# PDB2.net
KiCad netlist of a schematic drawn in EAGLE
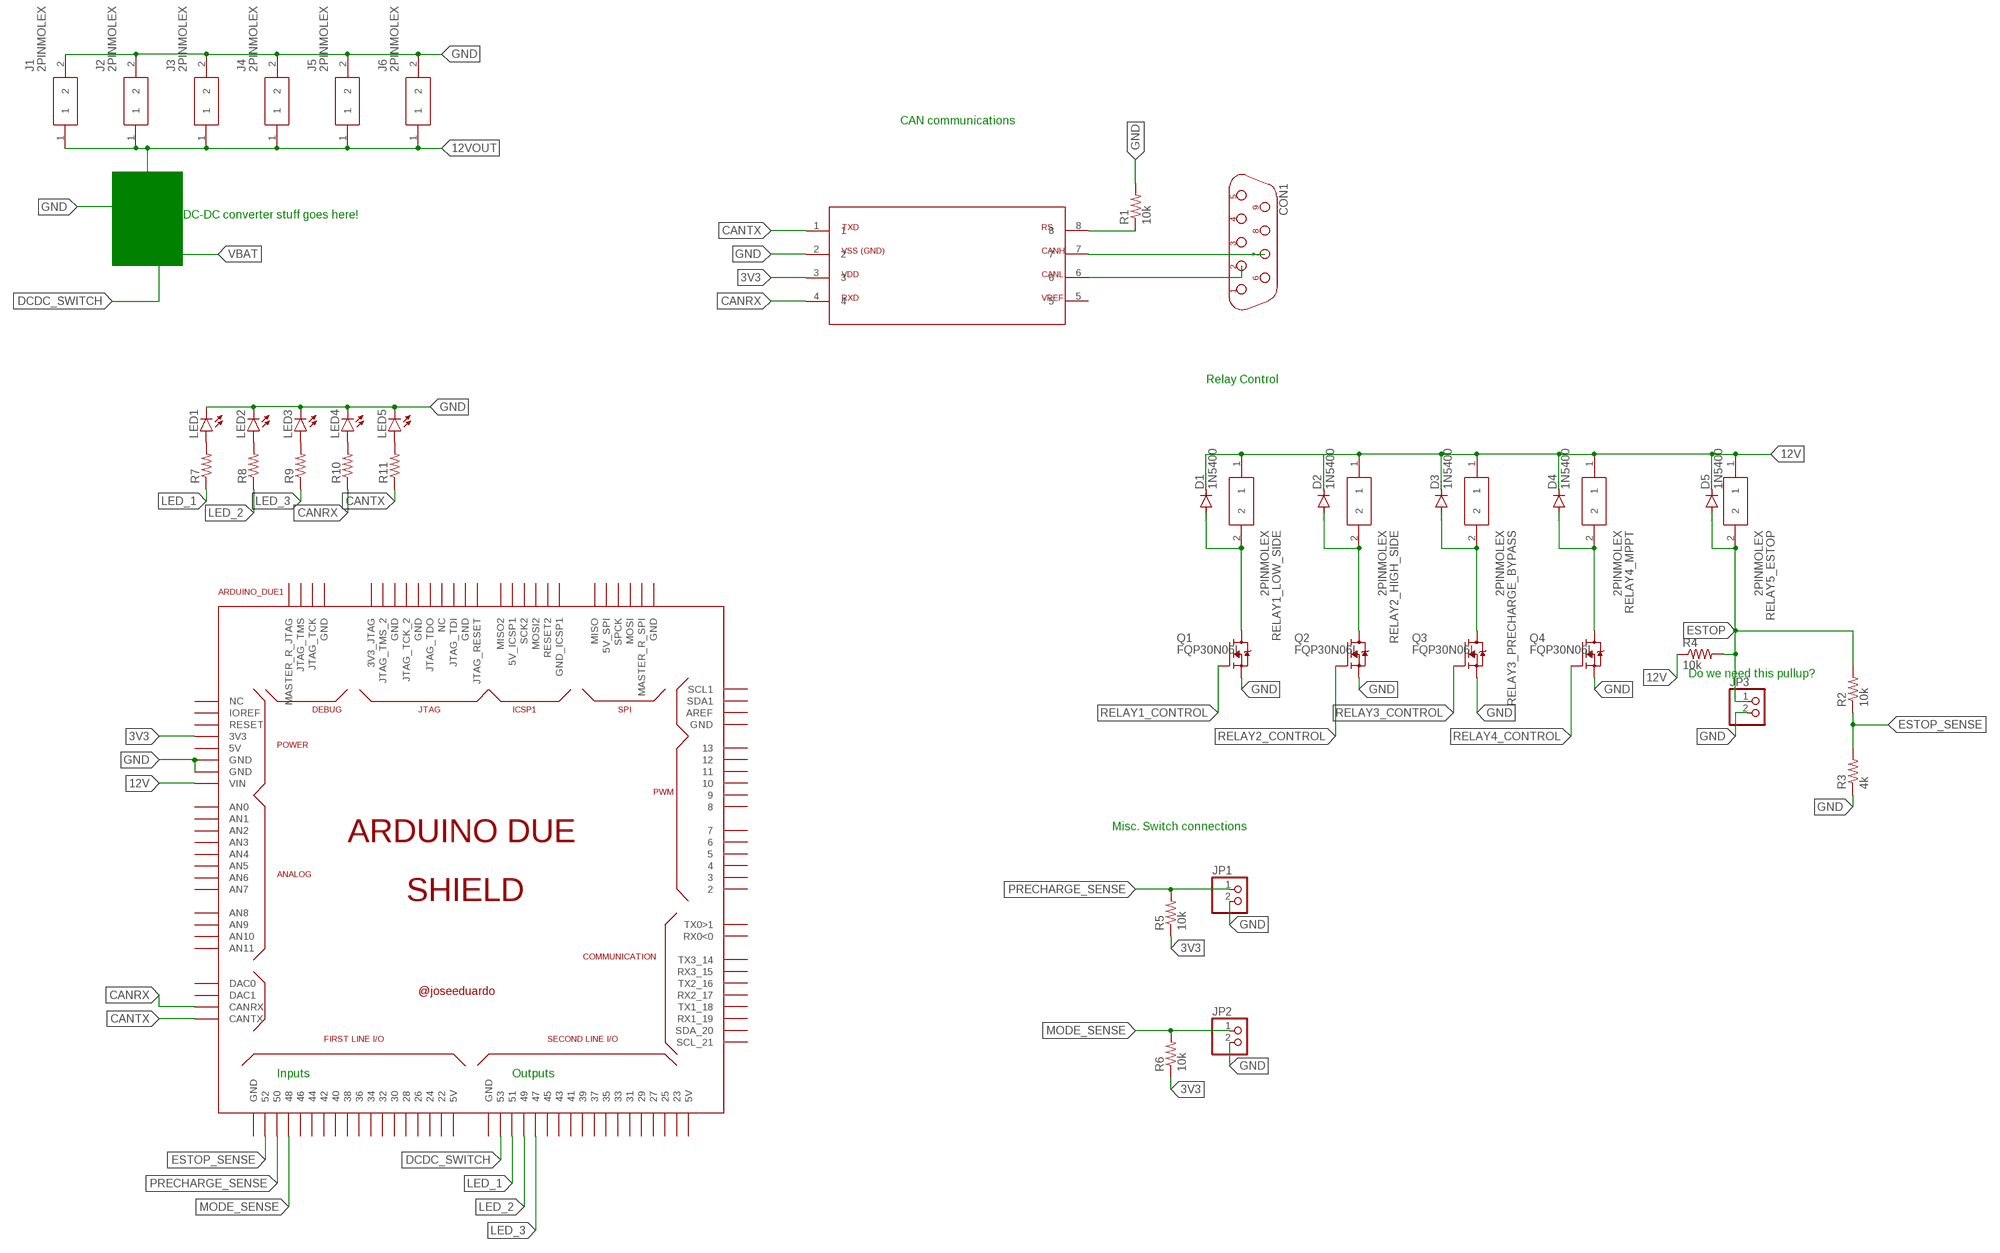
[diagram p0: schematic, sheet 1]

(export (version "E")
  (design (tool "Eeschema 10.0.6"))
  (components
    (comp (ref "ARDUINO_DUE1")
      (value "ARDUINO_DUE_SHIELD")
      (footprint "eagle-import:ARDUINO_DUE_SHIELD")
      (libsource (lib "eagle-import") (part "ARDUINO_DUE_SHIELD"))
    )
    (comp (ref "CON1")
      (value "DB9F")
      (footprint "eagle-import:D-09F")
      (libsource (lib "eagle-import") (part "DB9F"))
    )
    (comp (ref "D1")
      (value "1N5400")
      (footprint "eagle-import:DO201-15")
      (libsource (lib "eagle-import") (part "1N5400"))
    )
    (comp (ref "D2")
      (value "1N5400")
      (footprint "eagle-import:DO201-15")
      (libsource (lib "eagle-import") (part "1N5400"))
    )
    (comp (ref "D3")
      (value "1N5400")
      (footprint "eagle-import:DO201-15")
      (libsource (lib "eagle-import") (part "1N5400"))
    )
    (comp (ref "D4")
      (value "1N5400")
      (footprint "eagle-import:DO201-15")
      (libsource (lib "eagle-import") (part "1N5400"))
    )
    (comp (ref "D5")
      (value "1N5400")
      (footprint "eagle-import:DO201-15")
      (libsource (lib "eagle-import") (part "1N5400"))
    )
    (comp (ref "J1")
      (value "2PINMOLEX")
      (footprint "eagle-import:768250002")
      (fields
        (field (name "MANUFACTURER_PART_NUMBER") "76825-0002")
        (field (name "MOUSER_PART_NUMBER") "538-76825-0002")
        (field (name "RS_PART_NUMBER") "1790654")
      )
      (libsource (lib "eagle-import") (part "2PINMOLEX"))
    )
    (comp (ref "J2")
      (value "2PINMOLEX")
      (footprint "eagle-import:768250002")
      (fields
        (field (name "MANUFACTURER_PART_NUMBER") "76825-0002")
        (field (name "MOUSER_PART_NUMBER") "538-76825-0002")
        (field (name "RS_PART_NUMBER") "1790654")
      )
      (libsource (lib "eagle-import") (part "2PINMOLEX"))
    )
    (comp (ref "J3")
      (value "2PINMOLEX")
      (footprint "eagle-import:768250002")
      (fields
        (field (name "MANUFACTURER_PART_NUMBER") "76825-0002")
        (field (name "MOUSER_PART_NUMBER") "538-76825-0002")
        (field (name "RS_PART_NUMBER") "1790654")
      )
      (libsource (lib "eagle-import") (part "2PINMOLEX"))
    )
    (comp (ref "J4")
      (value "2PINMOLEX")
      (footprint "eagle-import:768250002")
      (fields
        (field (name "MANUFACTURER_PART_NUMBER") "76825-0002")
        (field (name "MOUSER_PART_NUMBER") "538-76825-0002")
        (field (name "RS_PART_NUMBER") "1790654")
      )
      (libsource (lib "eagle-import") (part "2PINMOLEX"))
    )
    (comp (ref "J5")
      (value "2PINMOLEX")
      (footprint "eagle-import:768250002")
      (fields
        (field (name "MANUFACTURER_PART_NUMBER") "76825-0002")
        (field (name "MOUSER_PART_NUMBER") "538-76825-0002")
        (field (name "RS_PART_NUMBER") "1790654")
      )
      (libsource (lib "eagle-import") (part "2PINMOLEX"))
    )
    (comp (ref "J6")
      (value "2PINMOLEX")
      (footprint "eagle-import:768250002")
      (fields
        (field (name "MANUFACTURER_PART_NUMBER") "76825-0002")
        (field (name "MOUSER_PART_NUMBER") "538-76825-0002")
        (field (name "RS_PART_NUMBER") "1790654")
      )
      (libsource (lib "eagle-import") (part "2PINMOLEX"))
    )
    (comp (ref "JP1")
      (value "PINHD-1X2")
      (footprint "eagle-import:1X02")
      (libsource (lib "eagle-import") (part "PINHD-1X2"))
    )
    (comp (ref "JP2")
      (value "PINHD-1X2")
      (footprint "eagle-import:1X02")
      (libsource (lib "eagle-import") (part "PINHD-1X2"))
    )
    (comp (ref "JP3")
      (value "PINHD-1X2")
      (footprint "eagle-import:1X02")
      (libsource (lib "eagle-import") (part "PINHD-1X2"))
    )
    (comp (ref "LED1")
      (value "LED5MM")
      (footprint "eagle-import:LED5MM")
      (libsource (lib "eagle-import") (part "LED5MM"))
    )
    (comp (ref "LED2")
      (value "LED5MM")
      (footprint "eagle-import:LED5MM")
      (libsource (lib "eagle-import") (part "LED5MM"))
    )
    (comp (ref "LED3")
      (value "LED5MM")
      (footprint "eagle-import:LED5MM")
      (libsource (lib "eagle-import") (part "LED5MM"))
    )
    (comp (ref "LED4")
      (value "LED5MM")
      (footprint "eagle-import:LED5MM")
      (libsource (lib "eagle-import") (part "LED5MM"))
    )
    (comp (ref "LED5")
      (value "LED5MM")
      (footprint "eagle-import:LED5MM")
      (libsource (lib "eagle-import") (part "LED5MM"))
    )
    (comp (ref "Q1")
      (value "FQP30N06L")
      (footprint "eagle-import:TO220V")
      (fields (field (name "MF") "ON Semiconductor"))
      (libsource (lib "eagle-import") (part "FQP30N06L"))
    )
    (comp (ref "Q2")
      (value "FQP30N06L")
      (footprint "eagle-import:TO220V")
      (fields (field (name "MF") "ON Semiconductor"))
      (libsource (lib "eagle-import") (part "FQP30N06L"))
    )
    (comp (ref "Q3")
      (value "FQP30N06L")
      (footprint "eagle-import:TO220V")
      (fields (field (name "MF") "ON Semiconductor"))
      (libsource (lib "eagle-import") (part "FQP30N06L"))
    )
    (comp (ref "Q4")
      (value "FQP30N06L")
      (footprint "eagle-import:TO220V")
      (fields (field (name "MF") "ON Semiconductor"))
      (libsource (lib "eagle-import") (part "FQP30N06L"))
    )
    (comp (ref "R1")
      (value "10k")
      (footprint "eagle-import:0204_7")
      (libsource (lib "eagle-import") (part "resistor_348_R-US_0204/7"))
    )
    (comp (ref "R2")
      (value "10k")
      (footprint "eagle-import:0204_7")
      (libsource (lib "eagle-import") (part "resistor_348_R-US_0204/7"))
    )
    (comp (ref "R3")
      (value "4k")
      (footprint "eagle-import:0204_7")
      (libsource (lib "eagle-import") (part "resistor_348_R-US_0204/7"))
    )
    (comp (ref "R4")
      (value "10k")
      (footprint "eagle-import:0204_7")
      (libsource (lib "eagle-import") (part "resistor_348_R-US_0204/7"))
    )
    (comp (ref "R5")
      (value "10k")
      (footprint "eagle-import:0204_7")
      (libsource (lib "eagle-import") (part "resistor_348_R-US_0204/7"))
    )
    (comp (ref "R6")
      (value "10k")
      (footprint "eagle-import:0204_7")
      (libsource (lib "eagle-import") (part "resistor_348_R-US_0204/7"))
    )
    (comp (ref "R7")
      (value "R-US_0204/7")
      (footprint "eagle-import:0204_7")
      (libsource (lib "eagle-import") (part "R-US_0204/7"))
    )
    (comp (ref "R8")
      (value "R-US_0204/7")
      (footprint "eagle-import:0204_7")
      (libsource (lib "eagle-import") (part "R-US_0204/7"))
    )
    (comp (ref "R9")
      (value "R-US_0204/7")
      (footprint "eagle-import:0204_7")
      (libsource (lib "eagle-import") (part "R-US_0204/7"))
    )
    (comp (ref "R10")
      (value "R-US_0204/7")
      (footprint "eagle-import:0204_7")
      (libsource (lib "eagle-import") (part "R-US_0204/7"))
    )
    (comp (ref "R11")
      (value "R-US_0204/7")
      (footprint "eagle-import:0204_7")
      (libsource (lib "eagle-import") (part "R-US_0204/7"))
    )
    (comp (ref "RELAY1_LOW_SIDE")
      (value "2PINMOLEX")
      (footprint "eagle-import:768250002")
      (fields
        (field (name "MANUFACTURER_PART_NUMBER") "76825-0002")
        (field (name "MOUSER_PART_NUMBER") "538-76825-0002")
        (field (name "RS_PART_NUMBER") "1790654")
      )
      (libsource (lib "eagle-import") (part "2PINMOLEX"))
    )
    (comp (ref "RELAY2_HIGH_SIDE")
      (value "2PINMOLEX")
      (footprint "eagle-import:768250002")
      (fields
        (field (name "MANUFACTURER_PART_NUMBER") "76825-0002")
        (field (name "MOUSER_PART_NUMBER") "538-76825-0002")
        (field (name "RS_PART_NUMBER") "1790654")
      )
      (libsource (lib "eagle-import") (part "2PINMOLEX"))
    )
    (comp (ref "RELAY3_PRECHARGE_BYPASS")
      (value "2PINMOLEX")
      (footprint "eagle-import:768250002")
      (fields
        (field (name "MANUFACTURER_PART_NUMBER") "76825-0002")
        (field (name "MOUSER_PART_NUMBER") "538-76825-0002")
        (field (name "RS_PART_NUMBER") "1790654")
      )
      (libsource (lib "eagle-import") (part "2PINMOLEX"))
    )
    (comp (ref "RELAY4_MPPT")
      (value "2PINMOLEX")
      (footprint "eagle-import:768250002")
      (fields
        (field (name "MANUFACTURER_PART_NUMBER") "76825-0002")
        (field (name "MOUSER_PART_NUMBER") "538-76825-0002")
        (field (name "RS_PART_NUMBER") "1790654")
      )
      (libsource (lib "eagle-import") (part "2PINMOLEX"))
    )
    (comp (ref "RELAY5_ESTOP")
      (value "2PINMOLEX")
      (footprint "eagle-import:768250002")
      (fields
        (field (name "MANUFACTURER_PART_NUMBER") "76825-0002")
        (field (name "MOUSER_PART_NUMBER") "538-76825-0002")
        (field (name "RS_PART_NUMBER") "1790654")
      )
      (libsource (lib "eagle-import") (part "2PINMOLEX"))
    )
    (comp (ref "U$1")
      (value "3.3VTRANSOIC-8")
      (footprint "eagle-import:SOIC8")
      (libsource (lib "eagle-import") (part "3.3VTRANSOIC-8"))
    )
  )
  (nets
    (net (code "1") (name "3V3") (class "Default")
      (node (ref "ARDUINO_DUE1") (pin "3V3") (pinfunction "3V3_3V3") (pintype "bidirectional"))
      (node (ref "R5") (pin "1") (pinfunction "1_1") (pintype "passive"))
      (node (ref "R6") (pin "1") (pinfunction "1_1") (pintype "passive"))
      (node (ref "U$1") (pin "3") (pinfunction "3_3") (pintype "bidirectional"))
    )
    (net (code "2") (name "12V") (class "Default")
      (node (ref "ARDUINO_DUE1") (pin "VIN") (pinfunction "VIN_VIN") (pintype "bidirectional"))
      (node (ref "D1") (pin "C") (pinfunction "C_C") (pintype "passive"))
      (node (ref "D2") (pin "C") (pinfunction "C_C") (pintype "passive"))
      (node (ref "D3") (pin "C") (pinfunction "C_C") (pintype "passive"))
      (node (ref "D4") (pin "C") (pinfunction "C_C") (pintype "passive"))
      (node (ref "D5") (pin "C") (pinfunction "C_C") (pintype "passive"))
      (node (ref "R4") (pin "1") (pinfunction "1_1") (pintype "passive"))
      (node (ref "RELAY1_LOW_SIDE") (pin "1") (pinfunction "1_1") (pintype "bidirectional"))
      (node (ref "RELAY2_HIGH_SIDE") (pin "1") (pinfunction "1_1") (pintype "bidirectional"))
      (node (ref "RELAY3_PRECHARGE_BYPASS") (pin "1") (pinfunction "1_1") (pintype "bidirectional"))
      (node (ref "RELAY4_MPPT") (pin "1") (pinfunction "1_1") (pintype "bidirectional"))
      (node (ref "RELAY5_ESTOP") (pin "1") (pinfunction "1_1") (pintype "bidirectional"))
    )
    (net (code "3") (name "12VOUT") (class "Default")
      (node (ref "J1") (pin "1") (pinfunction "1_1") (pintype "bidirectional"))
      (node (ref "J2") (pin "1") (pinfunction "1_1") (pintype "bidirectional"))
      (node (ref "J3") (pin "1") (pinfunction "1_1") (pintype "bidirectional"))
      (node (ref "J4") (pin "1") (pinfunction "1_1") (pintype "bidirectional"))
      (node (ref "J5") (pin "1") (pinfunction "1_1") (pintype "bidirectional"))
      (node (ref "J6") (pin "1") (pinfunction "1_1") (pintype "bidirectional"))
    )
    (net (code "4") (name "CANRX") (class "Default")
      (node (ref "ARDUINO_DUE1") (pin "CANRX") (pinfunction "CANRX_CANRX") (pintype "bidirectional"))
      (node (ref "R10") (pin "1") (pinfunction "1_1") (pintype "passive"))
      (node (ref "U$1") (pin "4") (pinfunction "4_4") (pintype "bidirectional"))
    )
    (net (code "5") (name "CANTX") (class "Default")
      (node (ref "ARDUINO_DUE1") (pin "CANTX") (pinfunction "CANTX_CANTX") (pintype "bidirectional"))
      (node (ref "R11") (pin "1") (pinfunction "1_1") (pintype "passive"))
      (node (ref "U$1") (pin "1") (pinfunction "1_1") (pintype "bidirectional"))
    )
    (net (code "6") (name "DCDC_SWITCH") (class "Default")
      (node (ref "ARDUINO_DUE1") (pin "53") (pinfunction "53_53") (pintype "bidirectional"))
    )
    (net (code "7") (name "ESTOP") (class "Default")
      (node (ref "D5") (pin "A") (pinfunction "A_A") (pintype "passive"))
      (node (ref "JP3") (pin "1") (pinfunction "1_1") (pintype "passive"))
      (node (ref "R2") (pin "2") (pinfunction "2_2") (pintype "passive"))
      (node (ref "R4") (pin "2") (pinfunction "2_2") (pintype "passive"))
      (node (ref "RELAY5_ESTOP") (pin "2") (pinfunction "2_2") (pintype "bidirectional"))
    )
    (net (code "8") (name "ESTOP_SENSE") (class "Default")
      (node (ref "ARDUINO_DUE1") (pin "52") (pinfunction "52_52") (pintype "bidirectional"))
      (node (ref "R2") (pin "1") (pinfunction "1_1") (pintype "passive"))
      (node (ref "R3") (pin "2") (pinfunction "2_2") (pintype "passive"))
    )
    (net (code "9") (name "GND") (class "Default")
      (node (ref "ARDUINO_DUE1") (pin "GND") (pinfunction "GND_GND") (pintype "bidirectional"))
      (node (ref "ARDUINO_DUE1") (pin "GND_1") (pinfunction "GND_GND_1") (pintype "bidirectional"))
      (node (ref "J1") (pin "2") (pinfunction "2_2") (pintype "bidirectional"))
      (node (ref "J2") (pin "2") (pinfunction "2_2") (pintype "bidirectional"))
      (node (ref "J3") (pin "2") (pinfunction "2_2") (pintype "bidirectional"))
      (node (ref "J4") (pin "2") (pinfunction "2_2") (pintype "bidirectional"))
      (node (ref "J5") (pin "2") (pinfunction "2_2") (pintype "bidirectional"))
      (node (ref "J6") (pin "2") (pinfunction "2_2") (pintype "bidirectional"))
      (node (ref "JP1") (pin "2") (pinfunction "2_2") (pintype "passive"))
      (node (ref "JP2") (pin "2") (pinfunction "2_2") (pintype "passive"))
      (node (ref "JP3") (pin "2") (pinfunction "2_2") (pintype "passive"))
      (node (ref "LED1") (pin "K") (pinfunction "C_K") (pintype "passive"))
      (node (ref "LED2") (pin "K") (pinfunction "C_K") (pintype "passive"))
      (node (ref "LED3") (pin "K") (pinfunction "C_K") (pintype "passive"))
      (node (ref "LED4") (pin "K") (pinfunction "C_K") (pintype "passive"))
      (node (ref "LED5") (pin "K") (pinfunction "C_K") (pintype "passive"))
      (node (ref "Q1") (pin "3") (pinfunction "S_3") (pintype "passive"))
      (node (ref "Q2") (pin "3") (pinfunction "S_3") (pintype "passive"))
      (node (ref "Q3") (pin "3") (pinfunction "S_3") (pintype "passive"))
      (node (ref "Q4") (pin "3") (pinfunction "S_3") (pintype "passive"))
      (node (ref "R1") (pin "2") (pinfunction "2_2") (pintype "passive"))
      (node (ref "R3") (pin "1") (pinfunction "1_1") (pintype "passive"))
      (node (ref "U$1") (pin "2") (pinfunction "2_2") (pintype "bidirectional"))
    )
    (net (code "10") (name "LED_1") (class "Default")
      (node (ref "ARDUINO_DUE1") (pin "51") (pinfunction "51_51") (pintype "bidirectional"))
      (node (ref "R7") (pin "1") (pinfunction "1_1") (pintype "passive"))
    )
    (net (code "11") (name "LED_2") (class "Default")
      (node (ref "ARDUINO_DUE1") (pin "49") (pinfunction "49_49") (pintype "bidirectional"))
      (node (ref "R8") (pin "1") (pinfunction "1_1") (pintype "passive"))
    )
    (net (code "12") (name "LED_3") (class "Default")
      (node (ref "ARDUINO_DUE1") (pin "47") (pinfunction "47_47") (pintype "bidirectional"))
      (node (ref "R9") (pin "1") (pinfunction "1_1") (pintype "passive"))
    )
    (net (code "13") (name "MODE_SENSE") (class "Default")
      (node (ref "ARDUINO_DUE1") (pin "48") (pinfunction "48_48") (pintype "bidirectional"))
      (node (ref "JP2") (pin "1") (pinfunction "1_1") (pintype "passive"))
      (node (ref "R6") (pin "2") (pinfunction "2_2") (pintype "passive"))
    )
    (net (code "14") (name "Net-(CON1-Pad2)") (class "Default")
      (node (ref "CON1") (pin "2") (pinfunction "2_2") (pintype "passive"))
      (node (ref "U$1") (pin "6") (pinfunction "6_6") (pintype "bidirectional"))
    )
    (net (code "15") (name "Net-(CON1-Pad7)") (class "Default")
      (node (ref "CON1") (pin "7") (pinfunction "7_7") (pintype "passive"))
      (node (ref "U$1") (pin "7") (pinfunction "7_7") (pintype "bidirectional"))
    )
    (net (code "16") (name "Net-(LED1-PadA)") (class "Default")
      (node (ref "LED1") (pin "A") (pinfunction "A_A") (pintype "passive"))
      (node (ref "R7") (pin "2") (pinfunction "2_2") (pintype "passive"))
    )
    (net (code "17") (name "Net-(LED2-PadA)") (class "Default")
      (node (ref "LED2") (pin "A") (pinfunction "A_A") (pintype "passive"))
      (node (ref "R8") (pin "2") (pinfunction "2_2") (pintype "passive"))
    )
    (net (code "18") (name "Net-(LED3-PadA)") (class "Default")
      (node (ref "LED3") (pin "A") (pinfunction "A_A") (pintype "passive"))
      (node (ref "R9") (pin "2") (pinfunction "2_2") (pintype "passive"))
    )
    (net (code "19") (name "Net-(LED4-PadA)") (class "Default")
      (node (ref "LED4") (pin "A") (pinfunction "A_A") (pintype "passive"))
      (node (ref "R10") (pin "2") (pinfunction "2_2") (pintype "passive"))
    )
    (net (code "20") (name "Net-(LED5-PadA)") (class "Default")
      (node (ref "LED5") (pin "A") (pinfunction "A_A") (pintype "passive"))
      (node (ref "R11") (pin "2") (pinfunction "2_2") (pintype "passive"))
    )
    (net (code "21") (name "Net-(Q1-D)") (class "Default")
      (node (ref "D1") (pin "A") (pinfunction "A_A") (pintype "passive"))
      (node (ref "Q1") (pin "2") (pinfunction "D_2") (pintype "passive"))
      (node (ref "RELAY1_LOW_SIDE") (pin "2") (pinfunction "2_2") (pintype "bidirectional"))
    )
    (net (code "22") (name "Net-(Q2-D)") (class "Default")
      (node (ref "D2") (pin "A") (pinfunction "A_A") (pintype "passive"))
      (node (ref "Q2") (pin "2") (pinfunction "D_2") (pintype "passive"))
      (node (ref "RELAY2_HIGH_SIDE") (pin "2") (pinfunction "2_2") (pintype "bidirectional"))
    )
    (net (code "23") (name "Net-(Q3-D)") (class "Default")
      (node (ref "D3") (pin "A") (pinfunction "A_A") (pintype "passive"))
      (node (ref "Q3") (pin "2") (pinfunction "D_2") (pintype "passive"))
      (node (ref "RELAY3_PRECHARGE_BYPASS") (pin "2") (pinfunction "2_2") (pintype "bidirectional"))
    )
    (net (code "24") (name "Net-(Q4-D)") (class "Default")
      (node (ref "D4") (pin "A") (pinfunction "A_A") (pintype "passive"))
      (node (ref "Q4") (pin "2") (pinfunction "D_2") (pintype "passive"))
      (node (ref "RELAY4_MPPT") (pin "2") (pinfunction "2_2") (pintype "bidirectional"))
    )
    (net (code "25") (name "Net-(R1-Pad1)") (class "Default")
      (node (ref "R1") (pin "1") (pinfunction "1_1") (pintype "passive"))
      (node (ref "U$1") (pin "8") (pinfunction "8_8") (pintype "bidirectional"))
    )
    (net (code "26") (name "PRECHARGE_SENSE") (class "Default")
      (node (ref "ARDUINO_DUE1") (pin "50") (pinfunction "50_50") (pintype "bidirectional"))
      (node (ref "JP1") (pin "1") (pinfunction "1_1") (pintype "passive"))
      (node (ref "R5") (pin "2") (pinfunction "2_2") (pintype "passive"))
    )
    (net (code "27") (name "RELAY1_CONTROL") (class "Default")
      (node (ref "Q1") (pin "1") (pinfunction "G_1") (pintype "passive"))
    )
    (net (code "28") (name "RELAY2_CONTROL") (class "Default")
      (node (ref "Q2") (pin "1") (pinfunction "G_1") (pintype "passive"))
    )
    (net (code "29") (name "RELAY3_CONTROL") (class "Default")
      (node (ref "Q3") (pin "1") (pinfunction "G_1") (pintype "passive"))
    )
    (net (code "30") (name "RELAY4_CONTROL") (class "Default")
      (node (ref "Q4") (pin "1") (pinfunction "G_1") (pintype "passive"))
    )
    (net (code "32") (name "unconnected-(ARDUINO_DUE1-5V-Pad5V0)") (class "Default")
      (node (ref "ARDUINO_DUE1") (pin "5V0") (pinfunction "5V_5V0") (pintype "bidirectional"))
    )
    (net (code "33") (name "unconnected-(ARDUINO_DUE1-5V-Pad5V0_1)") (class "Default")
      (node (ref "ARDUINO_DUE1") (pin "5V0_1") (pinfunction "5V_5V0_1") (pintype "bidirectional"))
    )
    (net (code "34") (name "unconnected-(ARDUINO_DUE1-5V-Pad5V0_2)") (class "Default")
      (node (ref "ARDUINO_DUE1") (pin "5V0_2") (pinfunction "5V_5V0_2") (pintype "bidirectional"))
    )
    (net (code "35") (name "unconnected-(ARDUINO_DUE1-5V_SPI-Pad5V_2)") (class "Default")
      (node (ref "ARDUINO_DUE1") (pin "5V_2") (pinfunction "5V_SPI_5V_2") (pintype "bidirectional"))
    )
    (net (code "36") (name "unconnected-(ARDUINO_DUE1-AN0-PadA0)") (class "Default")
      (node (ref "ARDUINO_DUE1") (pin "A0") (pinfunction "AN0_A0") (pintype "bidirectional"))
    )
    (net (code "37") (name "unconnected-(ARDUINO_DUE1-AN1-PadA1)") (class "Default")
      (node (ref "ARDUINO_DUE1") (pin "A1") (pinfunction "AN1_A1") (pintype "bidirectional"))
    )
    (net (code "38") (name "unconnected-(ARDUINO_DUE1-AN2-PadA2)") (class "Default")
      (node (ref "ARDUINO_DUE1") (pin "A2") (pinfunction "AN2_A2") (pintype "bidirectional"))
    )
    (net (code "39") (name "unconnected-(ARDUINO_DUE1-AN3-PadA3)") (class "Default")
      (node (ref "ARDUINO_DUE1") (pin "A3") (pinfunction "AN3_A3") (pintype "bidirectional"))
    )
    (net (code "40") (name "unconnected-(ARDUINO_DUE1-AN4-PadA4)") (class "Default")
      (node (ref "ARDUINO_DUE1") (pin "A4") (pinfunction "AN4_A4") (pintype "bidirectional"))
    )
    (net (code "41") (name "unconnected-(ARDUINO_DUE1-AN5-PadA5)") (class "Default")
      (node (ref "ARDUINO_DUE1") (pin "A5") (pinfunction "AN5_A5") (pintype "bidirectional"))
    )
    (net (code "42") (name "unconnected-(ARDUINO_DUE1-AN6-PadA6)") (class "Default")
      (node (ref "ARDUINO_DUE1") (pin "A6") (pinfunction "AN6_A6") (pintype "bidirectional"))
    )
    (net (code "43") (name "unconnected-(ARDUINO_DUE1-AN7-PadA7)") (class "Default")
      (node (ref "ARDUINO_DUE1") (pin "A7") (pinfunction "AN7_A7") (pintype "bidirectional"))
    )
    (net (code "44") (name "unconnected-(ARDUINO_DUE1-AN8-PadA8)") (class "Default")
      (node (ref "ARDUINO_DUE1") (pin "A8") (pinfunction "AN8_A8") (pintype "bidirectional"))
    )
    (net (code "45") (name "unconnected-(ARDUINO_DUE1-AN9-PadA9)") (class "Default")
      (node (ref "ARDUINO_DUE1") (pin "A9") (pinfunction "AN9_A9") (pintype "bidirectional"))
    )
    (net (code "46") (name "unconnected-(ARDUINO_DUE1-AN10-PadA10)") (class "Default")
      (node (ref "ARDUINO_DUE1") (pin "A10") (pinfunction "AN10_A10") (pintype "bidirectional"))
    )
    (net (code "47") (name "unconnected-(ARDUINO_DUE1-AN11-PadA11)") (class "Default")
      (node (ref "ARDUINO_DUE1") (pin "A11") (pinfunction "AN11_A11") (pintype "bidirectional"))
    )
    (net (code "48") (name "unconnected-(ARDUINO_DUE1-GND-PadGND_2)") (class "Default")
      (node (ref "ARDUINO_DUE1") (pin "GND_2") (pinfunction "GND_GND_2") (pintype "bidirectional"))
    )
    (net (code "49") (name "unconnected-(ARDUINO_DUE1-GND-PadGND_3)") (class "Default")
      (node (ref "ARDUINO_DUE1") (pin "GND_3") (pinfunction "GND_GND_3") (pintype "bidirectional"))
    )
    (net (code "50") (name "unconnected-(ARDUINO_DUE1-GND-PadGND_4)") (class "Default")
      (node (ref "ARDUINO_DUE1") (pin "GND_4") (pinfunction "GND_GND_4") (pintype "bidirectional"))
    )
    (net (code "51") (name "unconnected-(ARDUINO_DUE1-GND-PadGND_5)") (class "Default")
      (node (ref "ARDUINO_DUE1") (pin "GND_5") (pinfunction "GND_GND_5") (pintype "bidirectional"))
    )
    (net (code "52") (name "unconnected-(ARDUINO_DUE1-GND-PadGND_7)") (class "Default")
      (node (ref "ARDUINO_DUE1") (pin "GND_7") (pinfunction "GND_GND_7") (pintype "bidirectional"))
    )
    (net (code "53") (name "unconnected-(ARDUINO_DUE1-GND-PadGND_8)") (class "Default")
      (node (ref "ARDUINO_DUE1") (pin "GND_8") (pinfunction "GND_GND_8") (pintype "bidirectional"))
    )
    (net (code "54") (name "unconnected-(ARDUINO_DUE1-GND-PadGND_9)") (class "Default")
      (node (ref "ARDUINO_DUE1") (pin "GND_9") (pinfunction "GND_GND_9") (pintype "bidirectional"))
    )
    (net (code "55") (name "unconnected-(ARDUINO_DUE1-GND-PadGND_10)") (class "Default")
      (node (ref "ARDUINO_DUE1") (pin "GND_10") (pinfunction "GND_GND_10") (pintype "bidirectional"))
    )
    (net (code "56") (name "unconnected-(ARDUINO_DUE1-MASTER_R_JTAG-PadMASTER_RESET_JTAG)") (class "Default")
      (node (ref "ARDUINO_DUE1") (pin "MASTER_RESET_JTAG") (pinfunction "MASTER_R_JTAG_MASTER_RESET_JTAG") (pintype "bidirectional"))
    )
    (net (code "57") (name "unconnected-(ARDUINO_DUE1-MASTER_R_SPI-PadMASTER_RESET_SPI)") (class "Default")
      (node (ref "ARDUINO_DUE1") (pin "MASTER_RESET_SPI") (pinfunction "MASTER_R_SPI_MASTER_RESET_SPI") (pintype "bidirectional"))
    )
    (net (code "58") (name "unconnected-(ARDUINO_DUE1-NC-PadNC_2)") (class "Default")
      (node (ref "ARDUINO_DUE1") (pin "NC_2") (pinfunction "NC_NC_2") (pintype "no_connect"))
    )
    (net (code "59") (name "unconnected-(ARDUINO_DUE1-NC-PadNC_5)") (class "Default")
      (node (ref "ARDUINO_DUE1") (pin "NC_5") (pinfunction "NC_NC_5") (pintype "bidirectional"))
    )
    (net (code "60") (name "unconnected-(ARDUINO_DUE1-Pad2)") (class "Default")
      (node (ref "ARDUINO_DUE1") (pin "2") (pinfunction "2_2") (pintype "bidirectional"))
    )
    (net (code "61") (name "unconnected-(ARDUINO_DUE1-Pad3)") (class "Default")
      (node (ref "ARDUINO_DUE1") (pin "3") (pinfunction "3_3") (pintype "bidirectional"))
    )
    (net (code "62") (name "unconnected-(ARDUINO_DUE1-Pad3V3_JTAG)") (class "Default")
      (node (ref "ARDUINO_DUE1") (pin "3V3_JTAG") (pinfunction "3V3_JTAG_3V3_JTAG") (pintype "bidirectional"))
    )
    (net (code "63") (name "unconnected-(ARDUINO_DUE1-Pad4)") (class "Default")
      (node (ref "ARDUINO_DUE1") (pin "4") (pinfunction "4_4") (pintype "bidirectional"))
    )
    (net (code "64") (name "unconnected-(ARDUINO_DUE1-Pad5)") (class "Default")
      (node (ref "ARDUINO_DUE1") (pin "5") (pinfunction "5_5") (pintype "bidirectional"))
    )
    (net (code "65") (name "unconnected-(ARDUINO_DUE1-Pad5V_ICSP1)") (class "Default")
      (node (ref "ARDUINO_DUE1") (pin "5V_ICSP1") (pinfunction "5V_ICSP1_5V_ICSP1") (pintype "bidirectional"))
    )
    (net (code "66") (name "unconnected-(ARDUINO_DUE1-Pad6)") (class "Default")
      (node (ref "ARDUINO_DUE1") (pin "6") (pinfunction "6_6") (pintype "bidirectional"))
    )
    (net (code "67") (name "unconnected-(ARDUINO_DUE1-Pad7)") (class "Default")
      (node (ref "ARDUINO_DUE1") (pin "7") (pinfunction "7_7") (pintype "bidirectional"))
    )
    (net (code "68") (name "unconnected-(ARDUINO_DUE1-Pad8)") (class "Default")
      (node (ref "ARDUINO_DUE1") (pin "8") (pinfunction "8_8") (pintype "bidirectional"))
    )
    (net (code "69") (name "unconnected-(ARDUINO_DUE1-Pad9)") (class "Default")
      (node (ref "ARDUINO_DUE1") (pin "9") (pinfunction "9_9") (pintype "bidirectional"))
    )
    (net (code "70") (name "unconnected-(ARDUINO_DUE1-Pad10)") (class "Default")
      (node (ref "ARDUINO_DUE1") (pin "10") (pinfunction "10_10") (pintype "bidirectional"))
    )
    (net (code "71") (name "unconnected-(ARDUINO_DUE1-Pad11)") (class "Default")
      (node (ref "ARDUINO_DUE1") (pin "11") (pinfunction "11_11") (pintype "bidirectional"))
    )
    (net (code "72") (name "unconnected-(ARDUINO_DUE1-Pad12)") (class "Default")
      (node (ref "ARDUINO_DUE1") (pin "12") (pinfunction "12_12") (pintype "bidirectional"))
    )
    (net (code "73") (name "unconnected-(ARDUINO_DUE1-Pad13)") (class "Default")
      (node (ref "ARDUINO_DUE1") (pin "13") (pinfunction "13_13") (pintype "bidirectional"))
    )
    (net (code "74") (name "unconnected-(ARDUINO_DUE1-Pad22)") (class "Default")
      (node (ref "ARDUINO_DUE1") (pin "22") (pinfunction "22_22") (pintype "bidirectional"))
    )
    (net (code "75") (name "unconnected-(ARDUINO_DUE1-Pad23)") (class "Default")
      (node (ref "ARDUINO_DUE1") (pin "23") (pinfunction "23_23") (pintype "bidirectional"))
    )
    (net (code "76") (name "unconnected-(ARDUINO_DUE1-Pad24)") (class "Default")
      (node (ref "ARDUINO_DUE1") (pin "24") (pinfunction "24_24") (pintype "bidirectional"))
    )
    (net (code "77") (name "unconnected-(ARDUINO_DUE1-Pad25)") (class "Default")
      (node (ref "ARDUINO_DUE1") (pin "25") (pinfunction "25_25") (pintype "bidirectional"))
    )
    (net (code "78") (name "unconnected-(ARDUINO_DUE1-Pad26)") (class "Default")
      (node (ref "ARDUINO_DUE1") (pin "26") (pinfunction "26_26") (pintype "bidirectional"))
    )
    (net (code "79") (name "unconnected-(ARDUINO_DUE1-Pad27)") (class "Default")
      (node (ref "ARDUINO_DUE1") (pin "27") (pinfunction "27_27") (pintype "bidirectional"))
    )
    (net (code "80") (name "unconnected-(ARDUINO_DUE1-Pad28)") (class "Default")
      (node (ref "ARDUINO_DUE1") (pin "28") (pinfunction "28_28") (pintype "bidirectional"))
    )
    (net (code "81") (name "unconnected-(ARDUINO_DUE1-Pad29)") (class "Default")
      (node (ref "ARDUINO_DUE1") (pin "29") (pinfunction "29_29") (pintype "bidirectional"))
    )
    (net (code "82") (name "unconnected-(ARDUINO_DUE1-Pad30)") (class "Default")
      (node (ref "ARDUINO_DUE1") (pin "30") (pinfunction "30_30") (pintype "bidirectional"))
    )
    (net (code "83") (name "unconnected-(ARDUINO_DUE1-Pad31)") (class "Default")
      (node (ref "ARDUINO_DUE1") (pin "31") (pinfunction "31_31") (pintype "bidirectional"))
    )
    (net (code "84") (name "unconnected-(ARDUINO_DUE1-Pad32)") (class "Default")
      (node (ref "ARDUINO_DUE1") (pin "32") (pinfunction "32_32") (pintype "bidirectional"))
    )
    (net (code "85") (name "unconnected-(ARDUINO_DUE1-Pad33)") (class "Default")
      (node (ref "ARDUINO_DUE1") (pin "33") (pinfunction "33_33") (pintype "bidirectional"))
    )
    (net (code "86") (name "unconnected-(ARDUINO_DUE1-Pad34)") (class "Default")
      (node (ref "ARDUINO_DUE1") (pin "34") (pinfunction "34_34") (pintype "bidirectional"))
    )
    (net (code "87") (name "unconnected-(ARDUINO_DUE1-Pad35)") (class "Default")
      (node (ref "ARDUINO_DUE1") (pin "35") (pinfunction "35_35") (pintype "bidirectional"))
    )
    (net (code "88") (name "unconnected-(ARDUINO_DUE1-Pad36)") (class "Default")
      (node (ref "ARDUINO_DUE1") (pin "36") (pinfunction "36_36") (pintype "bidirectional"))
    )
    (net (code "89") (name "unconnected-(ARDUINO_DUE1-Pad37)") (class "Default")
      (node (ref "ARDUINO_DUE1") (pin "37") (pinfunction "37_37") (pintype "bidirectional"))
    )
    (net (code "90") (name "unconnected-(ARDUINO_DUE1-Pad38)") (class "Default")
      (node (ref "ARDUINO_DUE1") (pin "38") (pinfunction "38_38") (pintype "bidirectional"))
    )
    (net (code "91") (name "unconnected-(ARDUINO_DUE1-Pad39)") (class "Default")
      (node (ref "ARDUINO_DUE1") (pin "39") (pinfunction "39_39") (pintype "bidirectional"))
    )
    (net (code "92") (name "unconnected-(ARDUINO_DUE1-Pad40)") (class "Default")
      (node (ref "ARDUINO_DUE1") (pin "40") (pinfunction "40_40") (pintype "bidirectional"))
    )
    (net (code "93") (name "unconnected-(ARDUINO_DUE1-Pad41)") (class "Default")
      (node (ref "ARDUINO_DUE1") (pin "41") (pinfunction "41_41") (pintype "bidirectional"))
    )
    (net (code "94") (name "unconnected-(ARDUINO_DUE1-Pad42)") (class "Default")
      (node (ref "ARDUINO_DUE1") (pin "42") (pinfunction "42_42") (pintype "bidirectional"))
    )
    (net (code "95") (name "unconnected-(ARDUINO_DUE1-Pad43)") (class "Default")
      (node (ref "ARDUINO_DUE1") (pin "43") (pinfunction "43_43") (pintype "bidirectional"))
    )
    (net (code "96") (name "unconnected-(ARDUINO_DUE1-Pad44)") (class "Default")
      (node (ref "ARDUINO_DUE1") (pin "44") (pinfunction "44_44") (pintype "bidirectional"))
    )
    (net (code "97") (name "unconnected-(ARDUINO_DUE1-Pad45)") (class "Default")
      (node (ref "ARDUINO_DUE1") (pin "45") (pinfunction "45_45") (pintype "bidirectional"))
    )
    (net (code "98") (name "unconnected-(ARDUINO_DUE1-Pad46)") (class "Default")
      (node (ref "ARDUINO_DUE1") (pin "46") (pinfunction "46_46") (pintype "bidirectional"))
    )
    (net (code "99") (name "unconnected-(ARDUINO_DUE1-PadAREF)") (class "Default")
      (node (ref "ARDUINO_DUE1") (pin "AREF") (pinfunction "AREF_AREF") (pintype "bidirectional"))
    )
    (net (code "100") (name "unconnected-(ARDUINO_DUE1-PadDAC0)") (class "Default")
      (node (ref "ARDUINO_DUE1") (pin "DAC0") (pinfunction "DAC0_DAC0") (pintype "bidirectional"))
    )
    (net (code "101") (name "unconnected-(ARDUINO_DUE1-PadDAC1)") (class "Default")
      (node (ref "ARDUINO_DUE1") (pin "DAC1") (pinfunction "DAC1_DAC1") (pintype "bidirectional"))
    )
    (net (code "102") (name "unconnected-(ARDUINO_DUE1-PadGND_ICSP1)") (class "Default")
      (node (ref "ARDUINO_DUE1") (pin "GND_ICSP1") (pinfunction "GND_ICSP1_GND_ICSP1") (pintype "bidirectional"))
    )
    (net (code "103") (name "unconnected-(ARDUINO_DUE1-PadIOREF)") (class "Default")
      (node (ref "ARDUINO_DUE1") (pin "IOREF") (pinfunction "IOREF_IOREF") (pintype "bidirectional"))
    )
    (net (code "104") (name "unconnected-(ARDUINO_DUE1-PadJTAG_RESET)") (class "Default")
      (node (ref "ARDUINO_DUE1") (pin "JTAG_RESET") (pinfunction "JTAG_RESET_JTAG_RESET") (pintype "bidirectional"))
    )
    (net (code "105") (name "unconnected-(ARDUINO_DUE1-PadJTAG_TCK)") (class "Default")
      (node (ref "ARDUINO_DUE1") (pin "JTAG_TCK") (pinfunction "JTAG_TCK_JTAG_TCK") (pintype "bidirectional"))
    )
    (net (code "106") (name "unconnected-(ARDUINO_DUE1-PadJTAG_TCK_2)") (class "Default")
      (node (ref "ARDUINO_DUE1") (pin "JTAG_TCK_2") (pinfunction "JTAG_TCK_2_JTAG_TCK_2") (pintype "bidirectional"))
    )
    (net (code "107") (name "unconnected-(ARDUINO_DUE1-PadJTAG_TDI)") (class "Default")
      (node (ref "ARDUINO_DUE1") (pin "JTAG_TDI") (pinfunction "JTAG_TDI_JTAG_TDI") (pintype "bidirectional"))
    )
    (net (code "108") (name "unconnected-(ARDUINO_DUE1-PadJTAG_TDO)") (class "Default")
      (node (ref "ARDUINO_DUE1") (pin "JTAG_TDO") (pinfunction "JTAG_TDO_JTAG_TDO") (pintype "bidirectional"))
    )
    (net (code "109") (name "unconnected-(ARDUINO_DUE1-PadJTAG_TMS)") (class "Default")
      (node (ref "ARDUINO_DUE1") (pin "JTAG_TMS") (pinfunction "JTAG_TMS_JTAG_TMS") (pintype "bidirectional"))
    )
    (net (code "110") (name "unconnected-(ARDUINO_DUE1-PadJTAG_TMS_2)") (class "Default")
      (node (ref "ARDUINO_DUE1") (pin "JTAG_TMS_2") (pinfunction "JTAG_TMS_2_JTAG_TMS_2") (pintype "bidirectional"))
    )
    (net (code "111") (name "unconnected-(ARDUINO_DUE1-PadMISO)") (class "Default")
      (node (ref "ARDUINO_DUE1") (pin "MISO") (pinfunction "MISO_MISO") (pintype "bidirectional"))
    )
    (net (code "112") (name "unconnected-(ARDUINO_DUE1-PadMISO2)") (class "Default")
      (node (ref "ARDUINO_DUE1") (pin "MISO2") (pinfunction "MISO2_MISO2") (pintype "bidirectional"))
    )
    (net (code "113") (name "unconnected-(ARDUINO_DUE1-PadMOSI)") (class "Default")
      (node (ref "ARDUINO_DUE1") (pin "MOSI") (pinfunction "MOSI_MOSI") (pintype "bidirectional"))
    )
    (net (code "114") (name "unconnected-(ARDUINO_DUE1-PadMOSI2)") (class "Default")
      (node (ref "ARDUINO_DUE1") (pin "MOSI2") (pinfunction "MOSI2_MOSI2") (pintype "bidirectional"))
    )
    (net (code "115") (name "unconnected-(ARDUINO_DUE1-PadRESET)") (class "Default")
      (node (ref "ARDUINO_DUE1") (pin "RESET") (pinfunction "RESET_RESET") (pintype "bidirectional"))
    )
    (net (code "116") (name "unconnected-(ARDUINO_DUE1-PadRESET2)") (class "Default")
      (node (ref "ARDUINO_DUE1") (pin "RESET2") (pinfunction "RESET2_RESET2") (pintype "bidirectional"))
    )
    (net (code "117") (name "unconnected-(ARDUINO_DUE1-PadSCK2)") (class "Default")
      (node (ref "ARDUINO_DUE1") (pin "SCK2") (pinfunction "SCK2_SCK2") (pintype "bidirectional"))
    )
    (net (code "118") (name "unconnected-(ARDUINO_DUE1-PadSCL1)") (class "Default")
      (node (ref "ARDUINO_DUE1") (pin "SCL1") (pinfunction "SCL1_SCL1") (pintype "bidirectional"))
    )
    (net (code "119") (name "unconnected-(ARDUINO_DUE1-PadSDA1)") (class "Default")
      (node (ref "ARDUINO_DUE1") (pin "SDA1") (pinfunction "SDA1_SDA1") (pintype "bidirectional"))
    )
    (net (code "120") (name "unconnected-(ARDUINO_DUE1-PadSPCK)") (class "Default")
      (node (ref "ARDUINO_DUE1") (pin "SPCK") (pinfunction "SPCK_SPCK") (pintype "bidirectional"))
    )
    (net (code "121") (name "unconnected-(ARDUINO_DUE1-RX0<0-Pad0)") (class "Default")
      (node (ref "ARDUINO_DUE1") (pin "0") (pinfunction "RX0<0_0") (pintype "bidirectional"))
    )
    (net (code "122") (name "unconnected-(ARDUINO_DUE1-RX1_19-Pad19)") (class "Default")
      (node (ref "ARDUINO_DUE1") (pin "19") (pinfunction "RX1_19_19") (pintype "bidirectional"))
    )
    (net (code "123") (name "unconnected-(ARDUINO_DUE1-RX2_17-Pad17)") (class "Default")
      (node (ref "ARDUINO_DUE1") (pin "17") (pinfunction "RX2_17_17") (pintype "bidirectional"))
    )
    (net (code "124") (name "unconnected-(ARDUINO_DUE1-RX3_15-Pad15)") (class "Default")
      (node (ref "ARDUINO_DUE1") (pin "15") (pinfunction "RX3_15_15") (pintype "bidirectional"))
    )
    (net (code "125") (name "unconnected-(ARDUINO_DUE1-SCL_21-Pad21)") (class "Default")
      (node (ref "ARDUINO_DUE1") (pin "21") (pinfunction "SCL_21_21") (pintype "bidirectional"))
    )
    (net (code "126") (name "unconnected-(ARDUINO_DUE1-SDA_20-Pad20)") (class "Default")
      (node (ref "ARDUINO_DUE1") (pin "20") (pinfunction "SDA_20_20") (pintype "bidirectional"))
    )
    (net (code "127") (name "unconnected-(ARDUINO_DUE1-TX0>1-Pad1)") (class "Default")
      (node (ref "ARDUINO_DUE1") (pin "1") (pinfunction "TX0>1_1") (pintype "bidirectional"))
    )
    (net (code "128") (name "unconnected-(ARDUINO_DUE1-TX1_18-Pad18)") (class "Default")
      (node (ref "ARDUINO_DUE1") (pin "18") (pinfunction "TX1_18_18") (pintype "bidirectional"))
    )
    (net (code "129") (name "unconnected-(ARDUINO_DUE1-TX2_16-Pad16)") (class "Default")
      (node (ref "ARDUINO_DUE1") (pin "16") (pinfunction "TX2_16_16") (pintype "bidirectional"))
    )
    (net (code "130") (name "unconnected-(ARDUINO_DUE1-TX3_14-Pad14)") (class "Default")
      (node (ref "ARDUINO_DUE1") (pin "14") (pinfunction "TX3_14_14") (pintype "bidirectional"))
    )
    (net (code "131") (name "unconnected-(CON1-Pad1)") (class "Default")
      (node (ref "CON1") (pin "1") (pinfunction "1_1") (pintype "passive"))
    )
    (net (code "132") (name "unconnected-(CON1-Pad3)") (class "Default")
      (node (ref "CON1") (pin "3") (pinfunction "3_3") (pintype "passive"))
    )
    (net (code "133") (name "unconnected-(CON1-Pad4)") (class "Default")
      (node (ref "CON1") (pin "4") (pinfunction "4_4") (pintype "passive"))
    )
    (net (code "134") (name "unconnected-(CON1-Pad5)") (class "Default")
      (node (ref "CON1") (pin "5") (pinfunction "5_5") (pintype "passive"))
    )
    (net (code "135") (name "unconnected-(CON1-Pad6)") (class "Default")
      (node (ref "CON1") (pin "6") (pinfunction "6_6") (pintype "passive"))
    )
    (net (code "136") (name "unconnected-(CON1-Pad8)") (class "Default")
      (node (ref "CON1") (pin "8") (pinfunction "8_8") (pintype "passive"))
    )
    (net (code "137") (name "unconnected-(CON1-Pad9)") (class "Default")
      (node (ref "CON1") (pin "9") (pinfunction "9_9") (pintype "passive"))
    )
    (net (code "138") (name "unconnected-(U$1-Pad5)") (class "Default")
      (node (ref "U$1") (pin "5") (pinfunction "5_5") (pintype "bidirectional"))
    )
  )
)
